# 1-Controller.net
KiCad netlist of a schematic drawn in Altium Designer
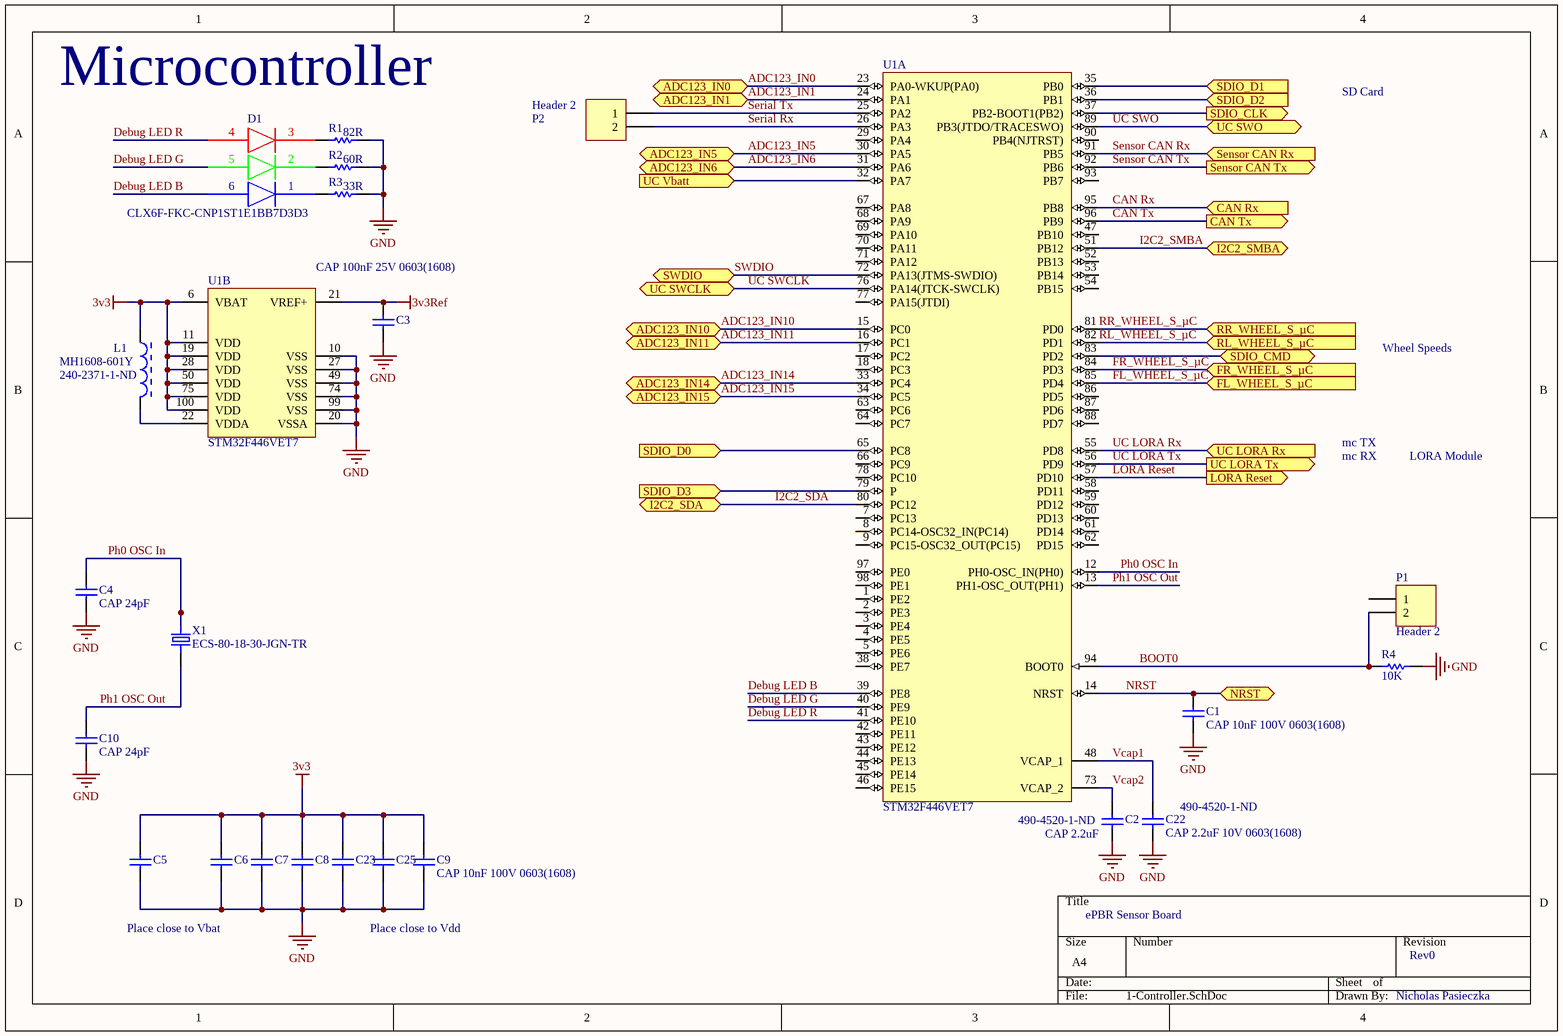
[diagram p0: 1-Controller.SchDoc]

(export (version "E")
  (design (tool "Eeschema 10.0.6"))
  (components
    (comp (ref "C1")
      (value "CAP 10nF 100V 0603(1608)")
      (footprint "CAPC0603(1608)100_M")
      (description "CAP 10nF 100V ±20% 0603 (1608 Metric) Thickness 1mm SMD")
      (fields (field (name "TOLERANCE") "Â±20%"))
      (libsource (lib "ECS-80-18-30-JGN-TR") (part "CAP"))
    )
    (comp (ref "C2")
      (value "CAP 2.2uF")
      (footprint "CAPC0603(1608)55_N")
      (description "CAP 2.2uF 10V ±10% 0603 (1608 Metric) Thickness 0.55mm SMD")
      (fields (field (name "TOLERANCE") "Â±10%") (field (name "SUPPLIER PART NUMBER 1") "490-4520-1-ND"))
      (libsource (lib "Altium Content Vault") (part "CAP"))
    )
    (comp (ref "C3")
      (value "CAP 100nF 25V 0603(1608)")
      (footprint "CAPC0603(1608)100_N")
      (description "CAP 100nF 25V ±20% 0603 (1608 Metric) Thickness 1mm SMD")
      (fields (field (name "TOLERANCE") "Â±20%"))
      (libsource (lib "Altium Content Vault") (part "CAP"))
    )
    (comp (ref "C4")
      (value "CAP 24pF")
      (footprint "CAPC0603(1608)100_N")
      (description "CAP 24pF 16V ±2% 0603 (1608 Metric) Thickness 1mm SMD")
      (fields (field (name "TOLERANCE") "Â±2%"))
      (libsource (lib "Altium Content Vault") (part "CAP"))
    )
    (comp (ref "C5")
      (value "CAP 10nF 100V 0603(1608)")
      (footprint "CAPC0603(1608)100_M")
      (description "CAP 10nF 100V ±20% 0603 (1608 Metric) Thickness 1mm SMD")
      (fields (field (name "TOLERANCE") "Â±20%"))
      (libsource (lib "Altium Content Vault") (part "CAP"))
    )
    (comp (ref "C6")
      (value "CAP 10nF 100V 0603(1608)")
      (footprint "CAPC0603(1608)100_M")
      (description "CAP 10nF 100V ±20% 0603 (1608 Metric) Thickness 1mm SMD")
      (fields (field (name "TOLERANCE") "Â±20%"))
      (libsource (lib "Altium Content Vault") (part "CAP"))
    )
    (comp (ref "C7")
      (value "CAP 10nF 100V 0603(1608)")
      (footprint "CAPC0603(1608)100_M")
      (description "CAP 10nF 100V ±20% 0603 (1608 Metric) Thickness 1mm SMD")
      (fields (field (name "TOLERANCE") "Â±20%"))
      (libsource (lib "Altium Content Vault") (part "CAP"))
    )
    (comp (ref "C8")
      (value "CAP 10nF 100V 0603(1608)")
      (footprint "CAPC0603(1608)100_M")
      (description "CAP 10nF 100V ±20% 0603 (1608 Metric) Thickness 1mm SMD")
      (fields (field (name "TOLERANCE") "Â±20%"))
      (libsource (lib "Altium Content Vault") (part "CAP"))
    )
    (comp (ref "C9")
      (value "CAP 10nF 100V 0603(1608)")
      (footprint "CAPC0603(1608)100_M")
      (description "CAP 10nF 100V ±20% 0603 (1608 Metric) Thickness 1mm SMD")
      (fields (field (name "TOLERANCE") "Â±20%"))
      (libsource (lib "Altium Content Vault") (part "CAP"))
    )
    (comp (ref "C10")
      (value "CAP 24pF")
      (footprint "CAPC0603(1608)100_N")
      (description "CAP 24pF 16V ±2% 0603 (1608 Metric) Thickness 1mm SMD")
      (fields (field (name "TOLERANCE") "Â±2%"))
      (libsource (lib "Altium Content Vault") (part "CAP"))
    )
    (comp (ref "C22")
      (value "CAP 2.2uF 10V 0603(1608)")
      (footprint "CAPC0603(1608)55_N")
      (description "CAP 2.2uF 10V ±10% 0603 (1608 Metric) Thickness 0.55mm SMD")
      (fields (field (name "TOLERANCE") "Â±10%") (field (name "SUPPLIER PART NUMBER 1") "490-4520-1-ND"))
      (libsource (lib "Altium Content Vault") (part "CAP"))
    )
    (comp (ref "C23")
      (value "CAP 10nF 100V 0603(1608)")
      (footprint "CAPC0603(1608)100_M")
      (description "CAP 10nF 100V ±20% 0603 (1608 Metric) Thickness 1mm SMD")
      (fields (field (name "TOLERANCE") "Â±20%"))
      (libsource (lib "Altium Content Vault") (part "CAP"))
    )
    (comp (ref "C25")
      (value "CAP 10nF 100V 0603(1608)")
      (footprint "CAPC0603(1608)100_M")
      (description "CAP 10nF 100V ±20% 0603 (1608 Metric) Thickness 1mm SMD")
      (fields (field (name "TOLERANCE") "Â±20%"))
      (libsource (lib "Altium Content Vault") (part "CAP"))
    )
    (comp (ref "D1")
      (value "CLX6F-FKC-CNP1ST1E1BB7D3D3")
      (footprint "CLX6C-FKB")
      (libsource (lib "VCB_2019") (part "LED - CLX6F-FKC-CNP1ST1E1BB7D3D3"))
    )
    (comp (ref "L1")
      (value "MH1608-601Y")
      (footprint "BOUR-MH1608_V")
      (description "Chip Bead, 600 Ohm, 1 A, -55 to 125 degC, 2-Pin SMD (0603), RoHS, Tape and Reel")
      (fields (field (name "MANUFACTURER") "Bourns") (field (name "SUPPLIER PART NUMBER 1") "240-2371-1-ND"))
      (libsource (lib "Altium Content Vault") (part "IND-FB-2"))
    )
    (comp (ref "P1")
      (value "Header 2")
      (footprint "HDR1X2")
      (description "Header, 2-Pin")
      (fields (field (name "PUBLISHER") "Altium Limited"))
      (libsource (lib "") (part "Header 2_1"))
    )
    (comp (ref "P2")
      (value "Header 2")
      (footprint "HDR1X2")
      (description "Header, 2-Pin")
      (fields (field (name "PUBLISHER") "Altium Limited"))
      (libsource (lib "Miscellaneous Connectors") (part "Header 2"))
    )
    (comp (ref "R1")
      (value "82R")
      (footprint "RESC0603(1608)_N")
      (description "82R 0.1W 5% 0603 (1608 Metric)  SMD")
      (fields (field (name "TOLERANCE") "5 %") (field (name "POWER") "0.1 W"))
      (libsource (lib "Altium Content Vault") (part "RES"))
    )
    (comp (ref "R2")
      (value "60R")
      (footprint "RESC0603(1608)_N")
      (description "60R4 0.1W 1% 0603 (1608 Metric)  SMD")
      (fields (field (name "TOLERANCE") "1 %") (field (name "POWER") "0.1 W"))
      (libsource (lib "Altium Content Vault") (part "RES"))
    )
    (comp (ref "R3")
      (value "33R")
      (footprint "RESC0603(1608)_N")
      (description "33R 0.1W 5% 0603 (1608 Metric)  SMD")
      (fields (field (name "TOLERANCE") "5 %") (field (name "POWER") "0.1 W"))
      (libsource (lib "Altium Content Vault") (part "RES"))
    )
    (comp (ref "R4")
      (value "10K")
      (footprint "RESC0603(1608)_N")
      (description "10K 0.1W 5% 0603 (1608 Metric)  SMD")
      (fields (field (name "TOLERANCE") "5 %") (field (name "POWER") "0.1 W"))
      (libsource (lib "Altium Content Vault") (part "RES"))
    )
    (comp (ref "U1")
      (value "STM32F446VET7")
      (footprint "STM-LQFP100_L")
      (libsource (lib "Altium Content Vault") (part "MC-ARM-STM32F446-LQFP100"))
    )
    (comp (ref "X1")
      (value "ECS-80-18-30-JGN-TR")
      (footprint "SnapEDApcb:XTAL_ECS-80-18-30-JGN-TR")
      (description "8MHz Â±20ppm Crystal 18pF 100 Ohms 2-SMD, No Lead")
      (fields (field (name "DIGI-KEY_PART_NUMBER") "XC2103CT-ND") (field (name "MF") "ECS Inc."))
      (libsource (lib "SnapEDAsch") (part "ECS-80-18-30-JGN-TR"))
    )
  )
  (nets
    (net (code "1") (name "/ADC123_IN0") (class "Default")
      (node (ref "U1") (pin "23") (pinfunction "PA0-WKUP(PA0)_23") (pintype "bidirectional"))
    )
    (net (code "2") (name "/ADC123_IN1") (class "Default")
      (node (ref "U1") (pin "24") (pinfunction "PA1_24") (pintype "bidirectional"))
    )
    (net (code "3") (name "/ADC123_IN5") (class "Default")
      (node (ref "U1") (pin "30") (pinfunction "PA5_30") (pintype "bidirectional"))
    )
    (net (code "4") (name "/ADC123_IN6") (class "Default")
      (node (ref "U1") (pin "31") (pinfunction "PA6_31") (pintype "bidirectional"))
    )
    (net (code "5") (name "/ADC123_IN10") (class "Default")
      (node (ref "U1") (pin "15") (pinfunction "PC0_15") (pintype "bidirectional"))
    )
    (net (code "6") (name "/ADC123_IN11") (class "Default")
      (node (ref "U1") (pin "16") (pinfunction "PC1_16") (pintype "bidirectional"))
    )
    (net (code "7") (name "/ADC123_IN14") (class "Default")
      (node (ref "U1") (pin "33") (pinfunction "PC4_33") (pintype "bidirectional"))
    )
    (net (code "8") (name "/ADC123_IN15") (class "Default")
      (node (ref "U1") (pin "34") (pinfunction "PC5_34") (pintype "bidirectional"))
    )
    (net (code "9") (name "/BOOT0") (class "Default")
      (node (ref "P1") (pin "2") (pinfunction "2_2") (pintype "passive"))
      (node (ref "R4") (pin "1") (pinfunction "1_1") (pintype "passive"))
      (node (ref "U1") (pin "94") (pinfunction "BOOT0_94") (pintype "input"))
    )
    (net (code "10") (name "/CAN Rx") (class "Default")
      (node (ref "U1") (pin "95") (pinfunction "PB8_95") (pintype "bidirectional"))
    )
    (net (code "11") (name "/CAN Tx") (class "Default")
      (node (ref "U1") (pin "96") (pinfunction "PB9_96") (pintype "bidirectional"))
    )
    (net (code "12") (name "/Debug LED B") (class "Default")
      (node (ref "D1") (pin "6") (pinfunction "B_6") (pintype "passive"))
      (node (ref "U1") (pin "39") (pinfunction "PE8_39") (pintype "bidirectional"))
    )
    (net (code "13") (name "/Debug LED G") (class "Default")
      (node (ref "D1") (pin "5") (pinfunction "G_5") (pintype "passive"))
      (node (ref "U1") (pin "40") (pinfunction "PE9_40") (pintype "bidirectional"))
    )
    (net (code "14") (name "/Debug LED R") (class "Default")
      (node (ref "D1") (pin "4") (pinfunction "R_4") (pintype "passive"))
      (node (ref "U1") (pin "41") (pinfunction "PE10_41") (pintype "bidirectional"))
    )
    (net (code "15") (name "/FL_WHEEL_S_µC") (class "Default")
      (node (ref "U1") (pin "85") (pinfunction "PD4_85") (pintype "bidirectional"))
    )
    (net (code "16") (name "/FR_WHEEL_S_µC") (class "Default")
      (node (ref "U1") (pin "84") (pinfunction "PD3_84") (pintype "bidirectional"))
    )
    (net (code "17") (name "/I2C2_SDA") (class "Default")
      (node (ref "U1") (pin "80") (pinfunction "PC12_80") (pintype "bidirectional"))
    )
    (net (code "18") (name "/I2C2_SMBA") (class "Default")
      (node (ref "U1") (pin "51") (pinfunction "PB12_51") (pintype "bidirectional"))
    )
    (net (code "19") (name "/LORA Reset") (class "Default")
      (node (ref "U1") (pin "57") (pinfunction "PD10_57") (pintype "bidirectional"))
    )
    (net (code "20") (name "/NRST") (class "Default")
      (node (ref "C1") (pin "2") (pinfunction "2_2") (pintype "passive"))
      (node (ref "U1") (pin "14") (pinfunction "NRST_14") (pintype "bidirectional"))
    )
    (net (code "21") (name "/Ph0 OSC In") (class "Default")
      (node (ref "C4") (pin "2") (pinfunction "2_2") (pintype "passive"))
      (node (ref "U1") (pin "12") (pinfunction "PH0-OSC_IN(PH0)_12") (pintype "bidirectional"))
      (node (ref "X1") (pin "2") (pinfunction "OUT/IN_2") (pintype "passive"))
    )
    (net (code "22") (name "/Ph1 OSC Out") (class "Default")
      (node (ref "C10") (pin "2") (pinfunction "2_2") (pintype "passive"))
      (node (ref "U1") (pin "13") (pinfunction "PH1-OSC_OUT(PH1)_13") (pintype "bidirectional"))
      (node (ref "X1") (pin "1") (pinfunction "IN/OUT_1") (pintype "passive"))
    )
    (net (code "23") (name "/RL_WHEEL_S_µC") (class "Default")
      (node (ref "U1") (pin "82") (pinfunction "PD1_82") (pintype "bidirectional"))
    )
    (net (code "24") (name "/RR_WHEEL_S_µC") (class "Default")
      (node (ref "U1") (pin "81") (pinfunction "PD0_81") (pintype "bidirectional"))
    )
    (net (code "25") (name "/SDIO_CLK") (class "Default")
      (node (ref "U1") (pin "37") (pinfunction "PB2-BOOT1(PB2)_37") (pintype "bidirectional"))
    )
    (net (code "26") (name "/SDIO_CMD") (class "Default")
      (node (ref "U1") (pin "83") (pinfunction "PD2_83") (pintype "bidirectional"))
    )
    (net (code "27") (name "/SDIO_D0") (class "Default")
      (node (ref "U1") (pin "65") (pinfunction "PC8_65") (pintype "bidirectional"))
    )
    (net (code "28") (name "/SDIO_D1") (class "Default")
      (node (ref "U1") (pin "35") (pinfunction "PB0_35") (pintype "bidirectional"))
    )
    (net (code "29") (name "/SDIO_D2") (class "Default")
      (node (ref "U1") (pin "36") (pinfunction "PB1_36") (pintype "bidirectional"))
    )
    (net (code "30") (name "/SDIO_D3") (class "Default")
      (node (ref "U1") (pin "79") (pinfunction "P_79") (pintype "bidirectional"))
    )
    (net (code "31") (name "/SWDIO") (class "Default")
      (node (ref "U1") (pin "72") (pinfunction "PA13(JTMS-SWDIO)_72") (pintype "bidirectional"))
    )
    (net (code "32") (name "/Sensor CAN Rx") (class "Default")
      (node (ref "U1") (pin "91") (pinfunction "PB5_91") (pintype "bidirectional"))
    )
    (net (code "33") (name "/Sensor CAN Tx") (class "Default")
      (node (ref "U1") (pin "92") (pinfunction "PB6_92") (pintype "bidirectional"))
    )
    (net (code "34") (name "/Serial Rx") (class "Default")
      (node (ref "P2") (pin "2") (pinfunction "2_2") (pintype "passive"))
      (node (ref "U1") (pin "26") (pinfunction "PA3_26") (pintype "bidirectional"))
    )
    (net (code "35") (name "/Serial Tx") (class "Default")
      (node (ref "P2") (pin "1") (pinfunction "1_1") (pintype "passive"))
      (node (ref "U1") (pin "25") (pinfunction "PA2_25") (pintype "bidirectional"))
    )
    (net (code "36") (name "/UC LORA Rx") (class "Default")
      (node (ref "U1") (pin "55") (pinfunction "PD8_55") (pintype "bidirectional"))
    )
    (net (code "37") (name "/UC LORA Tx") (class "Default")
      (node (ref "U1") (pin "56") (pinfunction "PD9_56") (pintype "bidirectional"))
    )
    (net (code "38") (name "/UC SWCLK") (class "Default")
      (node (ref "U1") (pin "76") (pinfunction "PA14(JTCK-SWCLK)_76") (pintype "bidirectional"))
    )
    (net (code "39") (name "/UC SWO") (class "Default")
      (node (ref "U1") (pin "89") (pinfunction "PB3(JTDO/TRACESWO)_89") (pintype "bidirectional"))
    )
    (net (code "40") (name "/UC Vbatt") (class "Default")
      (node (ref "U1") (pin "32") (pinfunction "PA7_32") (pintype "bidirectional"))
    )
    (net (code "41") (name "/Vcap1") (class "Default")
      (node (ref "C22") (pin "2") (pinfunction "2_2") (pintype "passive"))
      (node (ref "U1") (pin "48") (pinfunction "VCAP_1_48") (pintype "passive"))
    )
    (net (code "42") (name "/Vcap2") (class "Default")
      (node (ref "C2") (pin "2") (pinfunction "2_2") (pintype "passive"))
      (node (ref "U1") (pin "73") (pinfunction "VCAP_2_73") (pintype "passive"))
    )
    (net (code "43") (name "3v3") (class "Default")
      (node (ref "C23") (pin "2") (pinfunction "2_2") (pintype "passive"))
      (node (ref "C25") (pin "2") (pinfunction "2_2") (pintype "passive"))
      (node (ref "C5") (pin "2") (pinfunction "2_2") (pintype "passive"))
      (node (ref "C6") (pin "2") (pinfunction "2_2") (pintype "passive"))
      (node (ref "C7") (pin "2") (pinfunction "2_2") (pintype "passive"))
      (node (ref "C8") (pin "2") (pinfunction "2_2") (pintype "passive"))
      (node (ref "C9") (pin "2") (pinfunction "2_2") (pintype "passive"))
      (node (ref "L1") (pin "1") (pinfunction "1_1") (pintype "passive"))
      (node (ref "U1") (pin "100") (pinfunction "VDD_100") (pintype "power_in"))
      (node (ref "U1") (pin "11") (pinfunction "VDD_11") (pintype "power_in"))
      (node (ref "U1") (pin "19") (pinfunction "VDD_19") (pintype "power_in"))
      (node (ref "U1") (pin "28") (pinfunction "VDD_28") (pintype "power_in"))
      (node (ref "U1") (pin "50") (pinfunction "VDD_50") (pintype "power_in"))
      (node (ref "U1") (pin "6") (pinfunction "VBAT_6") (pintype "power_in"))
      (node (ref "U1") (pin "75") (pinfunction "VDD_75") (pintype "power_in"))
    )
    (net (code "44") (name "3v3Ref") (class "Default")
      (node (ref "C3") (pin "2") (pinfunction "2_2") (pintype "passive"))
      (node (ref "U1") (pin "21") (pinfunction "VREF+_21") (pintype "power_in"))
    )
    (net (code "45") (name "GND") (class "Default")
      (node (ref "C1") (pin "1") (pinfunction "1_1") (pintype "passive"))
      (node (ref "C10") (pin "1") (pinfunction "1_1") (pintype "passive"))
      (node (ref "C2") (pin "1") (pinfunction "1_1") (pintype "passive"))
      (node (ref "C22") (pin "1") (pinfunction "1_1") (pintype "passive"))
      (node (ref "C23") (pin "1") (pinfunction "1_1") (pintype "passive"))
      (node (ref "C25") (pin "1") (pinfunction "1_1") (pintype "passive"))
      (node (ref "C3") (pin "1") (pinfunction "1_1") (pintype "passive"))
      (node (ref "C4") (pin "1") (pinfunction "1_1") (pintype "passive"))
      (node (ref "C5") (pin "1") (pinfunction "1_1") (pintype "passive"))
      (node (ref "C6") (pin "1") (pinfunction "1_1") (pintype "passive"))
      (node (ref "C7") (pin "1") (pinfunction "1_1") (pintype "passive"))
      (node (ref "C8") (pin "1") (pinfunction "1_1") (pintype "passive"))
      (node (ref "C9") (pin "1") (pinfunction "1_1") (pintype "passive"))
      (node (ref "R1") (pin "2") (pinfunction "2_2") (pintype "passive"))
      (node (ref "R2") (pin "2") (pinfunction "2_2") (pintype "passive"))
      (node (ref "R3") (pin "2") (pinfunction "2_2") (pintype "passive"))
      (node (ref "R4") (pin "2") (pinfunction "2_2") (pintype "passive"))
      (node (ref "U1") (pin "10") (pinfunction "VSS_10") (pintype "power_in"))
      (node (ref "U1") (pin "20") (pinfunction "VSSA_20") (pintype "power_in"))
      (node (ref "U1") (pin "27") (pinfunction "VSS_27") (pintype "power_in"))
      (node (ref "U1") (pin "49") (pinfunction "VSS_49") (pintype "power_in"))
      (node (ref "U1") (pin "74") (pinfunction "VSS_74") (pintype "power_in"))
      (node (ref "U1") (pin "99") (pinfunction "VSS_99") (pintype "power_in"))
    )
    (net (code "46") (name "Net-(D1-B-Pad1)") (class "Default")
      (node (ref "D1") (pin "1") (pinfunction "B_1") (pintype "passive"))
      (node (ref "R3") (pin "1") (pinfunction "1_1") (pintype "passive"))
    )
    (net (code "47") (name "Net-(D1-G-Pad2)") (class "Default")
      (node (ref "D1") (pin "2") (pinfunction "G_2") (pintype "passive"))
      (node (ref "R2") (pin "1") (pinfunction "1_1") (pintype "passive"))
    )
    (net (code "48") (name "Net-(D1-R-Pad3)") (class "Default")
      (node (ref "D1") (pin "3") (pinfunction "R_3") (pintype "passive"))
      (node (ref "R1") (pin "1") (pinfunction "1_1") (pintype "passive"))
    )
    (net (code "49") (name "Net-(U1B-VDDA)") (class "Default")
      (node (ref "L1") (pin "2") (pinfunction "2_2") (pintype "passive"))
      (node (ref "U1") (pin "22") (pinfunction "VDDA_22") (pintype "power_in"))
    )
    (net (code "50") (name "unconnected-(P1-Pad1)") (class "Default")
      (node (ref "P1") (pin "1") (pinfunction "1_1") (pintype "passive"))
    )
    (net (code "51") (name "unconnected-(U1A-PA4-Pad29)") (class "Default")
      (node (ref "U1") (pin "29") (pinfunction "PA4_29") (pintype "bidirectional"))
    )
    (net (code "52") (name "unconnected-(U1A-PA8-Pad67)") (class "Default")
      (node (ref "U1") (pin "67") (pinfunction "PA8_67") (pintype "bidirectional"))
    )
    (net (code "53") (name "unconnected-(U1A-PA9-Pad68)") (class "Default")
      (node (ref "U1") (pin "68") (pinfunction "PA9_68") (pintype "bidirectional"))
    )
    (net (code "54") (name "unconnected-(U1A-PA10-Pad69)") (class "Default")
      (node (ref "U1") (pin "69") (pinfunction "PA10_69") (pintype "bidirectional"))
    )
    (net (code "55") (name "unconnected-(U1A-PA11-Pad70)") (class "Default")
      (node (ref "U1") (pin "70") (pinfunction "PA11_70") (pintype "bidirectional"))
    )
    (net (code "56") (name "unconnected-(U1A-PA12-Pad71)") (class "Default")
      (node (ref "U1") (pin "71") (pinfunction "PA12_71") (pintype "bidirectional"))
    )
    (net (code "57") (name "unconnected-(U1A-PA15(JTDI)-Pad77)") (class "Default")
      (node (ref "U1") (pin "77") (pinfunction "PA15(JTDI)_77") (pintype "bidirectional"))
    )
    (net (code "58") (name "unconnected-(U1A-PB4(NJTRST)-Pad90)") (class "Default")
      (node (ref "U1") (pin "90") (pinfunction "PB4(NJTRST)_90") (pintype "bidirectional"))
    )
    (net (code "59") (name "unconnected-(U1A-PB7-Pad93)") (class "Default")
      (node (ref "U1") (pin "93") (pinfunction "PB7_93") (pintype "bidirectional"))
    )
    (net (code "60") (name "unconnected-(U1A-PB10-Pad47)") (class "Default")
      (node (ref "U1") (pin "47") (pinfunction "PB10_47") (pintype "bidirectional"))
    )
    (net (code "61") (name "unconnected-(U1A-PB13-Pad52)") (class "Default")
      (node (ref "U1") (pin "52") (pinfunction "PB13_52") (pintype "bidirectional"))
    )
    (net (code "62") (name "unconnected-(U1A-PB14-Pad53)") (class "Default")
      (node (ref "U1") (pin "53") (pinfunction "PB14_53") (pintype "bidirectional"))
    )
    (net (code "63") (name "unconnected-(U1A-PB15-Pad54)") (class "Default")
      (node (ref "U1") (pin "54") (pinfunction "PB15_54") (pintype "bidirectional"))
    )
    (net (code "64") (name "unconnected-(U1A-PC2-Pad17)") (class "Default")
      (node (ref "U1") (pin "17") (pinfunction "PC2_17") (pintype "bidirectional"))
    )
    (net (code "65") (name "unconnected-(U1A-PC3-Pad18)") (class "Default")
      (node (ref "U1") (pin "18") (pinfunction "PC3_18") (pintype "bidirectional"))
    )
    (net (code "66") (name "unconnected-(U1A-PC6-Pad63)") (class "Default")
      (node (ref "U1") (pin "63") (pinfunction "PC6_63") (pintype "bidirectional"))
    )
    (net (code "67") (name "unconnected-(U1A-PC7-Pad64)") (class "Default")
      (node (ref "U1") (pin "64") (pinfunction "PC7_64") (pintype "bidirectional"))
    )
    (net (code "68") (name "unconnected-(U1A-PC9-Pad66)") (class "Default")
      (node (ref "U1") (pin "66") (pinfunction "PC9_66") (pintype "bidirectional"))
    )
    (net (code "69") (name "unconnected-(U1A-PC10-Pad78)") (class "Default")
      (node (ref "U1") (pin "78") (pinfunction "PC10_78") (pintype "bidirectional"))
    )
    (net (code "70") (name "unconnected-(U1A-PC13-Pad7)") (class "Default")
      (node (ref "U1") (pin "7") (pinfunction "PC13_7") (pintype "bidirectional"))
    )
    (net (code "71") (name "unconnected-(U1A-PC14-OSC32_IN(PC14)-Pad8)") (class "Default")
      (node (ref "U1") (pin "8") (pinfunction "PC14-OSC32_IN(PC14)_8") (pintype "bidirectional"))
    )
    (net (code "72") (name "unconnected-(U1A-PC15-OSC32_OUT(PC15)-Pad9)") (class "Default")
      (node (ref "U1") (pin "9") (pinfunction "PC15-OSC32_OUT(PC15)_9") (pintype "bidirectional"))
    )
    (net (code "73") (name "unconnected-(U1A-PD5-Pad86)") (class "Default")
      (node (ref "U1") (pin "86") (pinfunction "PD5_86") (pintype "bidirectional"))
    )
    (net (code "74") (name "unconnected-(U1A-PD6-Pad87)") (class "Default")
      (node (ref "U1") (pin "87") (pinfunction "PD6_87") (pintype "bidirectional"))
    )
    (net (code "75") (name "unconnected-(U1A-PD7-Pad88)") (class "Default")
      (node (ref "U1") (pin "88") (pinfunction "PD7_88") (pintype "bidirectional"))
    )
    (net (code "76") (name "unconnected-(U1A-PD11-Pad58)") (class "Default")
      (node (ref "U1") (pin "58") (pinfunction "PD11_58") (pintype "bidirectional"))
    )
    (net (code "77") (name "unconnected-(U1A-PD12-Pad59)") (class "Default")
      (node (ref "U1") (pin "59") (pinfunction "PD12_59") (pintype "bidirectional"))
    )
    (net (code "78") (name "unconnected-(U1A-PD13-Pad60)") (class "Default")
      (node (ref "U1") (pin "60") (pinfunction "PD13_60") (pintype "bidirectional"))
    )
    (net (code "79") (name "unconnected-(U1A-PD14-Pad61)") (class "Default")
      (node (ref "U1") (pin "61") (pinfunction "PD14_61") (pintype "bidirectional"))
    )
    (net (code "80") (name "unconnected-(U1A-PD15-Pad62)") (class "Default")
      (node (ref "U1") (pin "62") (pinfunction "PD15_62") (pintype "bidirectional"))
    )
    (net (code "81") (name "unconnected-(U1A-PE0-Pad97)") (class "Default")
      (node (ref "U1") (pin "97") (pinfunction "PE0_97") (pintype "bidirectional"))
    )
    (net (code "82") (name "unconnected-(U1A-PE1-Pad98)") (class "Default")
      (node (ref "U1") (pin "98") (pinfunction "PE1_98") (pintype "bidirectional"))
    )
    (net (code "83") (name "unconnected-(U1A-PE2-Pad1)") (class "Default")
      (node (ref "U1") (pin "1") (pinfunction "PE2_1") (pintype "bidirectional"))
    )
    (net (code "84") (name "unconnected-(U1A-PE3-Pad2)") (class "Default")
      (node (ref "U1") (pin "2") (pinfunction "PE3_2") (pintype "bidirectional"))
    )
    (net (code "85") (name "unconnected-(U1A-PE4-Pad3)") (class "Default")
      (node (ref "U1") (pin "3") (pinfunction "PE4_3") (pintype "bidirectional"))
    )
    (net (code "86") (name "unconnected-(U1A-PE5-Pad4)") (class "Default")
      (node (ref "U1") (pin "4") (pinfunction "PE5_4") (pintype "bidirectional"))
    )
    (net (code "87") (name "unconnected-(U1A-PE6-Pad5)") (class "Default")
      (node (ref "U1") (pin "5") (pinfunction "PE6_5") (pintype "bidirectional"))
    )
    (net (code "88") (name "unconnected-(U1A-PE7-Pad38)") (class "Default")
      (node (ref "U1") (pin "38") (pinfunction "PE7_38") (pintype "bidirectional"))
    )
    (net (code "89") (name "unconnected-(U1A-PE11-Pad42)") (class "Default")
      (node (ref "U1") (pin "42") (pinfunction "PE11_42") (pintype "bidirectional"))
    )
    (net (code "90") (name "unconnected-(U1A-PE12-Pad43)") (class "Default")
      (node (ref "U1") (pin "43") (pinfunction "PE12_43") (pintype "bidirectional"))
    )
    (net (code "91") (name "unconnected-(U1A-PE13-Pad44)") (class "Default")
      (node (ref "U1") (pin "44") (pinfunction "PE13_44") (pintype "bidirectional"))
    )
    (net (code "92") (name "unconnected-(U1A-PE14-Pad45)") (class "Default")
      (node (ref "U1") (pin "45") (pinfunction "PE14_45") (pintype "bidirectional"))
    )
    (net (code "93") (name "unconnected-(U1A-PE15-Pad46)") (class "Default")
      (node (ref "U1") (pin "46") (pinfunction "PE15_46") (pintype "bidirectional"))
    )
  )
)
